# p0-001.net
KiCad netlist of a schematic drawn in EAGLE
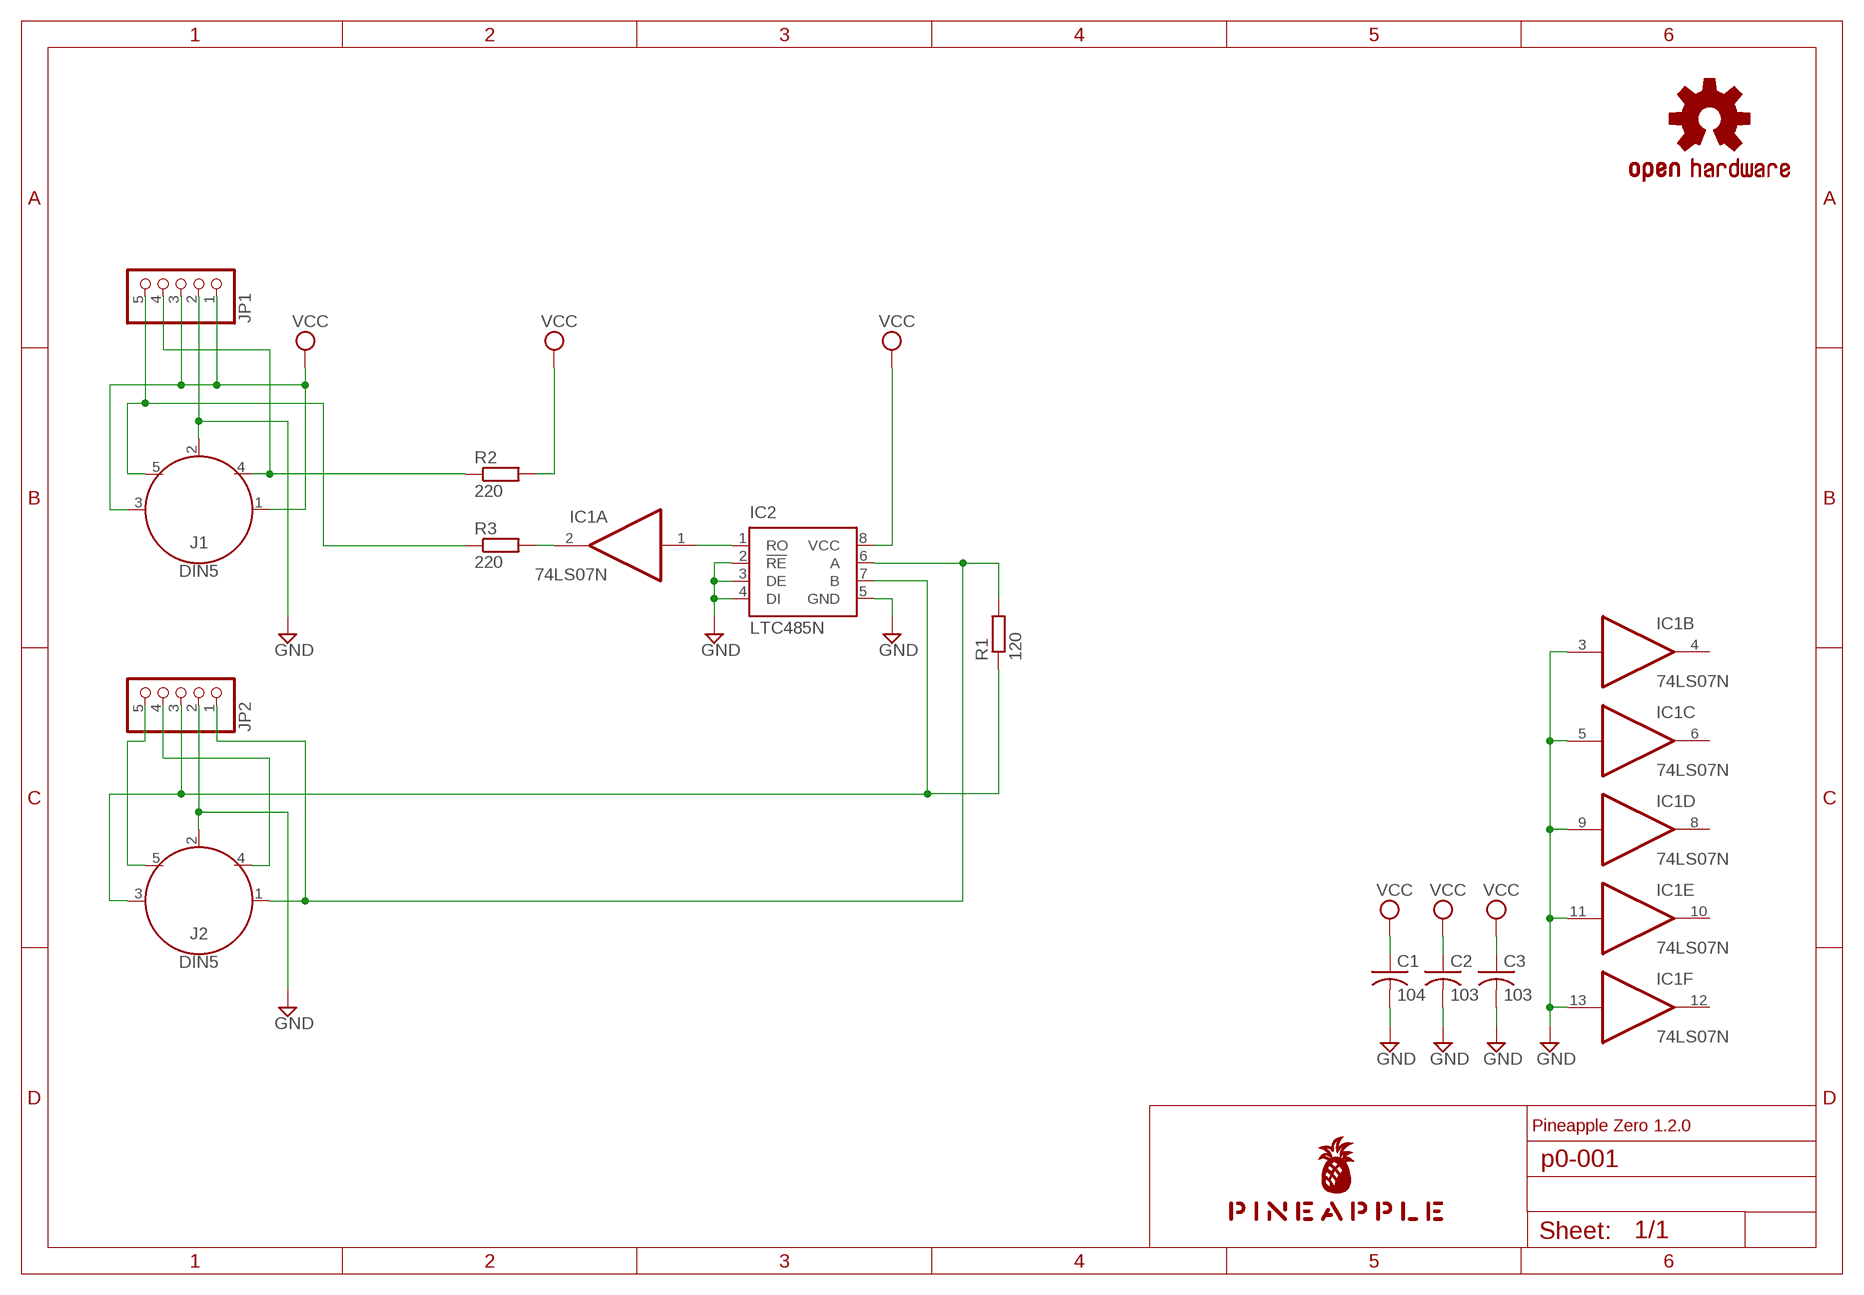
[diagram p0: schematic, sheet 1]

(export (version "E")
  (design (tool "Eeschema 10.0.6"))
  (components
    (comp (ref "C1")
      (value "104")
      (footprint "eagle-import:C025-025X050")
      (libsource (lib "eagle-import") (part "C-US025-025X050"))
    )
    (comp (ref "C2")
      (value "103")
      (footprint "eagle-import:C025-025X050")
      (libsource (lib "eagle-import") (part "C-US025-025X050"))
    )
    (comp (ref "C3")
      (value "103")
      (footprint "eagle-import:C025-025X050")
      (libsource (lib "eagle-import") (part "C-US025-025X050"))
    )
    (comp (ref "IC1")
      (value "74LS07N")
      (footprint "eagle-import:DIL14")
      (libsource (lib "eagle-import") (part "7407NLS"))
    )
    (comp (ref "IC2")
      (value "LTC485N")
      (footprint "eagle-import:DIL08")
      (libsource (lib "eagle-import") (part "LTC485N"))
    )
    (comp (ref "J1")
      (value "DIN5")
      (footprint "eagle-import:DIN5-RA-PTH")
      (libsource (lib "eagle-import") (part "DIN5"))
    )
    (comp (ref "J2")
      (value "DIN5")
      (footprint "eagle-import:DIN5-RA-PTH")
      (libsource (lib "eagle-import") (part "DIN5"))
    )
    (comp (ref "JP1")
      (value "PINHD-1X5")
      (footprint "eagle-import:1X05")
      (libsource (lib "eagle-import") (part "PINHD-1X5"))
    )
    (comp (ref "JP2")
      (value "PINHD-1X5")
      (footprint "eagle-import:1X05")
      (libsource (lib "eagle-import") (part "PINHD-1X5"))
    )
    (comp (ref "LOGO1")
      (value "OSHW-LOGOS-COPPER")
      (footprint "eagle-import:OSHW-LOGO-S_COPPER")
      (libsource (lib "eagle-import") (part "OSHW-LOGOS-COPPER"))
    )
    (comp (ref "R1")
      (value "120")
      (footprint "eagle-import:0204_5")
      (libsource (lib "eagle-import") (part "R-EU_0204/5"))
    )
    (comp (ref "R2")
      (value "220")
      (footprint "eagle-import:0204_5")
      (libsource (lib "eagle-import") (part "R-EU_0204/5"))
    )
    (comp (ref "R3")
      (value "220")
      (footprint "eagle-import:0204_5")
      (libsource (lib "eagle-import") (part "R-EU_0204/5"))
    )
    (comp (ref "U$1")
      (value "PINEAPPLE450")
      (footprint "eagle-import:PINEAPPLE450")
      (libsource (lib "eagle-import") (part "PINEAPPLE450"))
    )
  )
  (nets
    (net (code "1") (name "GND") (class "Default")
      (node (ref "C1") (pin "2") (pinfunction "2_2") (pintype "passive"))
      (node (ref "C2") (pin "2") (pinfunction "2_2") (pintype "passive"))
      (node (ref "C3") (pin "2") (pinfunction "2_2") (pintype "passive"))
      (node (ref "IC1") (pin "11") (pinfunction "I_11") (pintype "input"))
      (node (ref "IC1") (pin "13") (pinfunction "I_13") (pintype "input"))
      (node (ref "IC1") (pin "3") (pinfunction "I_3") (pintype "input"))
      (node (ref "IC1") (pin "5") (pinfunction "I_5") (pintype "input"))
      (node (ref "IC1") (pin "9") (pinfunction "I_9") (pintype "input"))
      (node (ref "IC2") (pin "2") (pinfunction "~{RE}_2") (pintype "input"))
      (node (ref "IC2") (pin "3") (pinfunction "DE_3") (pintype "input"))
      (node (ref "IC2") (pin "4") (pinfunction "DI_4") (pintype "input"))
      (node (ref "IC2") (pin "5") (pinfunction "GND_5") (pintype "input"))
      (node (ref "J1") (pin "2") (pinfunction "2_2") (pintype "bidirectional"))
      (node (ref "J2") (pin "2") (pinfunction "2_2") (pintype "bidirectional"))
      (node (ref "JP1") (pin "2") (pinfunction "2_2") (pintype "passive"))
      (node (ref "JP2") (pin "2") (pinfunction "2_2") (pintype "passive"))
    )
    (net (code "2") (name "Net-(IC1A-I)") (class "Default")
      (node (ref "IC1") (pin "1") (pinfunction "I_1") (pintype "input"))
      (node (ref "IC2") (pin "1") (pinfunction "RO_1") (pintype "output"))
    )
    (net (code "3") (name "Net-(IC1A-O)") (class "Default")
      (node (ref "IC1") (pin "2") (pinfunction "O_2") (pintype "open_collector"))
      (node (ref "R3") (pin "2") (pinfunction "2_2") (pintype "passive"))
    )
    (net (code "4") (name "Net-(IC2-A)") (class "Default")
      (node (ref "IC2") (pin "6") (pinfunction "A_6") (pintype "bidirectional"))
      (node (ref "J2") (pin "1") (pinfunction "1_1") (pintype "bidirectional"))
      (node (ref "JP2") (pin "1") (pinfunction "1_1") (pintype "passive"))
      (node (ref "R1") (pin "2") (pinfunction "2_2") (pintype "passive"))
    )
    (net (code "5") (name "Net-(IC2-B)") (class "Default")
      (node (ref "IC2") (pin "7") (pinfunction "B_7") (pintype "bidirectional"))
      (node (ref "J2") (pin "3") (pinfunction "3_3") (pintype "bidirectional"))
      (node (ref "JP2") (pin "3") (pinfunction "3_3") (pintype "passive"))
      (node (ref "R1") (pin "1") (pinfunction "1_1") (pintype "passive"))
    )
    (net (code "6") (name "Net-(J1-Pad4)") (class "Default")
      (node (ref "J1") (pin "4") (pinfunction "4_4") (pintype "bidirectional"))
      (node (ref "JP1") (pin "4") (pinfunction "4_4") (pintype "passive"))
      (node (ref "R2") (pin "1") (pinfunction "1_1") (pintype "passive"))
    )
    (net (code "7") (name "Net-(J1-Pad5)") (class "Default")
      (node (ref "J1") (pin "5") (pinfunction "5_5") (pintype "bidirectional"))
      (node (ref "JP1") (pin "5") (pinfunction "5_5") (pintype "passive"))
      (node (ref "R3") (pin "1") (pinfunction "1_1") (pintype "passive"))
    )
    (net (code "8") (name "Net-(J2-Pad4)") (class "Default")
      (node (ref "J2") (pin "4") (pinfunction "4_4") (pintype "bidirectional"))
      (node (ref "JP2") (pin "4") (pinfunction "4_4") (pintype "passive"))
    )
    (net (code "9") (name "Net-(J2-Pad5)") (class "Default")
      (node (ref "J2") (pin "5") (pinfunction "5_5") (pintype "bidirectional"))
      (node (ref "JP2") (pin "5") (pinfunction "5_5") (pintype "passive"))
    )
    (net (code "10") (name "VCC") (class "Default")
      (node (ref "C1") (pin "1") (pinfunction "1_1") (pintype "passive"))
      (node (ref "C2") (pin "1") (pinfunction "1_1") (pintype "passive"))
      (node (ref "C3") (pin "1") (pinfunction "1_1") (pintype "passive"))
      (node (ref "IC2") (pin "8") (pinfunction "VCC_8") (pintype "input"))
      (node (ref "J1") (pin "1") (pinfunction "1_1") (pintype "bidirectional"))
      (node (ref "J1") (pin "3") (pinfunction "3_3") (pintype "bidirectional"))
      (node (ref "JP1") (pin "1") (pinfunction "1_1") (pintype "passive"))
      (node (ref "JP1") (pin "3") (pinfunction "3_3") (pintype "passive"))
      (node (ref "R2") (pin "2") (pinfunction "2_2") (pintype "passive"))
    )
    (net (code "11") (name "unconnected-(IC1B-O-Pad4)") (class "Default")
      (node (ref "IC1") (pin "4") (pinfunction "O_4") (pintype "open_collector"))
    )
    (net (code "12") (name "unconnected-(IC1C-O-Pad6)") (class "Default")
      (node (ref "IC1") (pin "6") (pinfunction "O_6") (pintype "open_collector"))
    )
    (net (code "13") (name "unconnected-(IC1D-O-Pad8)") (class "Default")
      (node (ref "IC1") (pin "8") (pinfunction "O_8") (pintype "open_collector"))
    )
    (net (code "14") (name "unconnected-(IC1E-O-Pad10)") (class "Default")
      (node (ref "IC1") (pin "10") (pinfunction "O_10") (pintype "open_collector"))
    )
    (net (code "15") (name "unconnected-(IC1F-O-Pad12)") (class "Default")
      (node (ref "IC1") (pin "12") (pinfunction "O_12") (pintype "open_collector"))
    )
  )
)
